# BEP33_2panel_v2b_DESKTOP-T8KKGMJ_Mai-19-.net
KiCad netlist of a schematic drawn in EAGLE
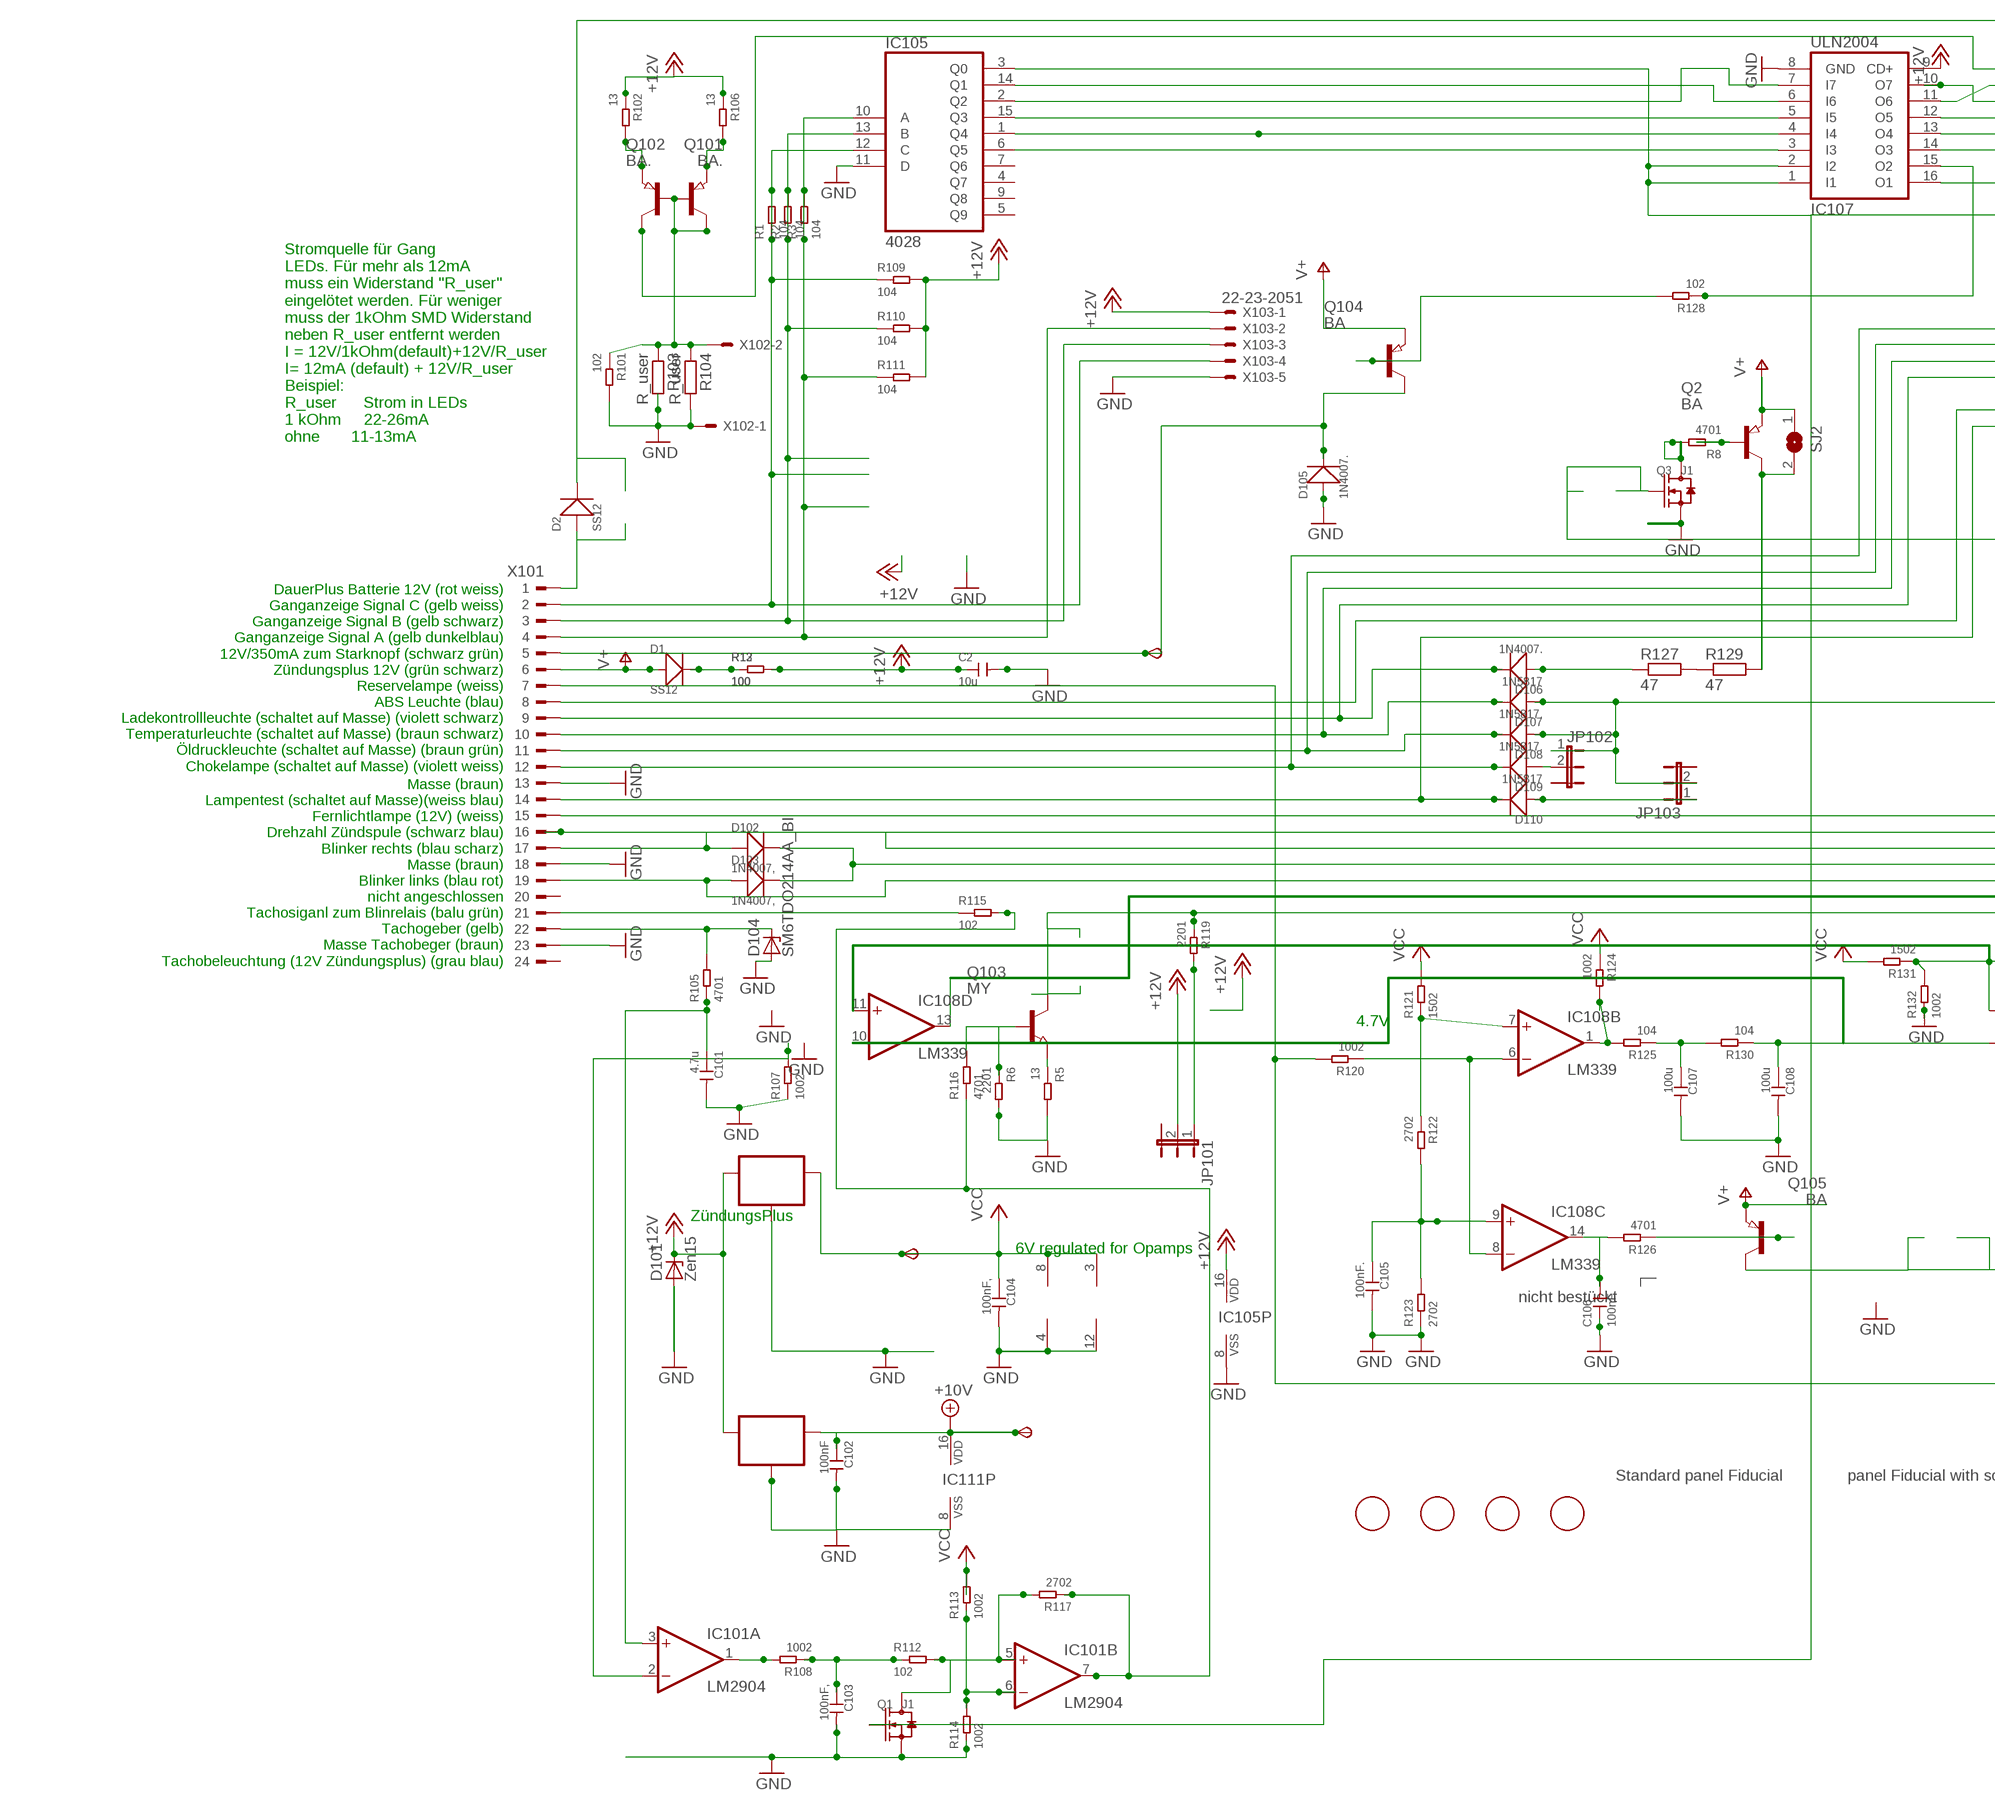
[diagram p0: schematic, sheet 1, part 1 of 2]
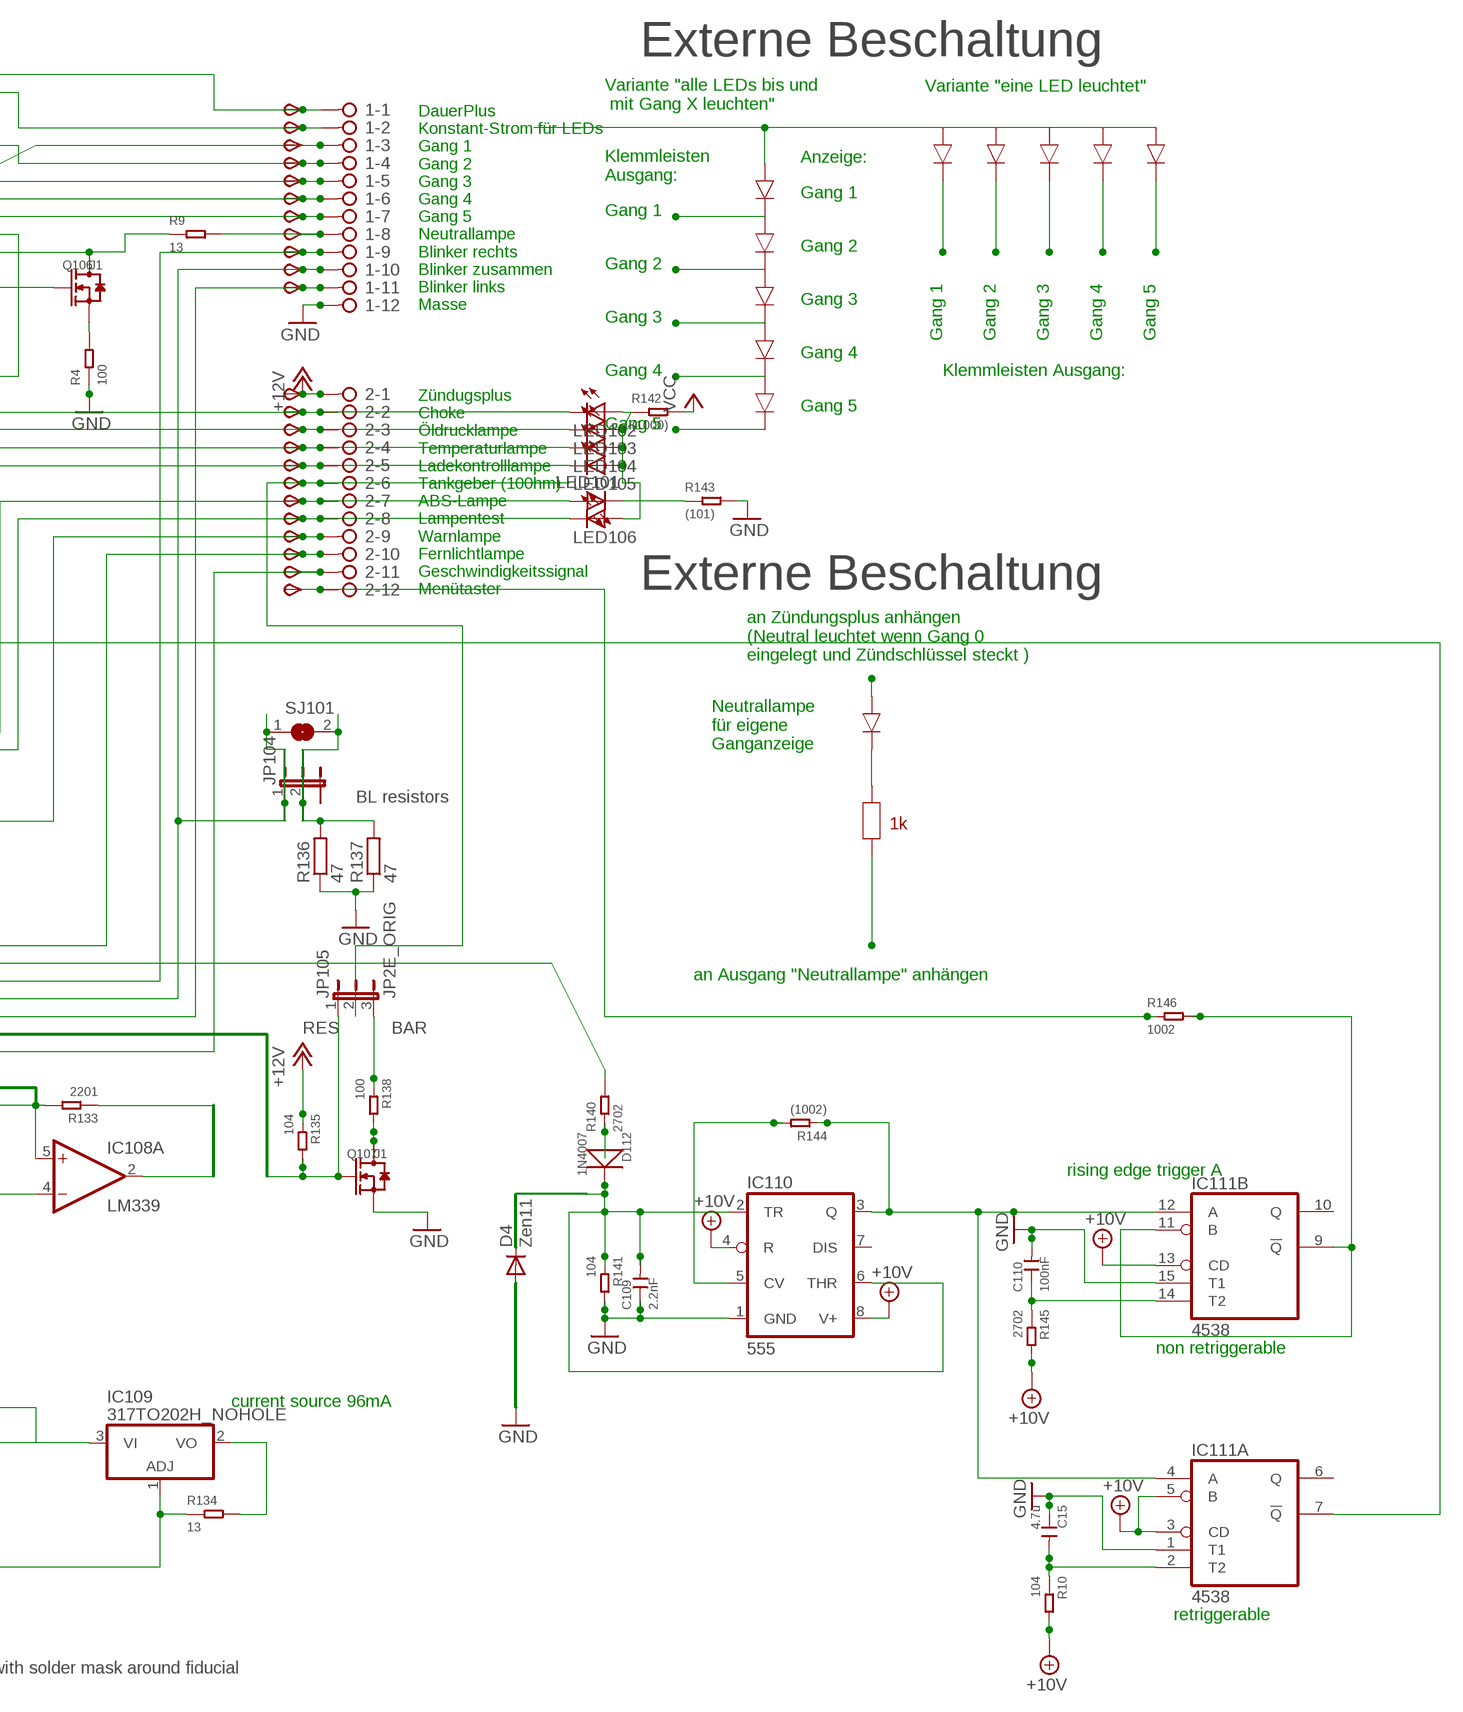
[diagram p1: schematic, sheet 1, part 2 of 2]

(export (version "E")
  (design (tool "Eeschema 10.0.6"))
  (components
    (comp (ref "1")
      (value "2081-1132")
      (footprint "eagle-import:12-PIN")
      (libsource (lib "eagle-import") (part "2081-1132"))
    )
    (comp (ref "2")
      (value "2081-1132")
      (footprint "eagle-import:12-PIN")
      (libsource (lib "eagle-import") (part "2081-1132"))
    )
    (comp (ref "6V")
      (value "TPSB2.0")
      (footprint "eagle-import:B2.0")
      (libsource (lib "eagle-import") (part "TPSB2.0"))
    )
    (comp (ref "10V")
      (value "TPSB2.0")
      (footprint "eagle-import:B2.0")
      (libsource (lib "eagle-import") (part "TPSB2.0"))
    )
    (comp (ref "C2")
      (value "10u")
      (footprint "eagle-import:C1206")
      (fields (field (name "MPN") "GRM31CR60J107ME39L"))
      (libsource (lib "eagle-import") (part "CERAMIC-100UF-6.3V-20%-X5R(1206)"))
    )
    (comp (ref "C15")
      (value "4.7u")
      (footprint "eagle-import:C0805")
      (fields (field (name "MPN") "CC0805KKX5R8BB475"))
      (libsource (lib "eagle-import") (part "CERAMIC-4.7UF-25V-10%-X5R(0805)"))
    )
    (comp (ref "C101")
      (value "4.7u")
      (footprint "eagle-import:C0805")
      (fields (field (name "MPN") "CC0805KKX5R8BB475"))
      (libsource (lib "eagle-import") (part "CERAMIC-4.7UF-25V-10%-X5R(0805)"))
    )
    (comp (ref "C102")
      (value "100nF")
      (footprint "eagle-import:C0805")
      (fields (field (name "MPN") "CC0805KRX7R9BB104"))
      (libsource (lib "eagle-import") (part "CERAMIC-100NF-50V-10%-X7R(0805)"))
    )
    (comp (ref "C103")
      (value "100nF,")
      (footprint "eagle-import:C0805")
      (fields (field (name "MPN") "CC0805KRX7R9BB104"))
      (libsource (lib "eagle-import") (part "CERAMIC-100NF-50V-10%-X7R(0805)"))
    )
    (comp (ref "C104")
      (value "100nF,")
      (footprint "eagle-import:C0805")
      (fields (field (name "MPN") "CC0805KRX7R9BB104"))
      (libsource (lib "eagle-import") (part "CERAMIC-100NF-50V-10%-X7R(0805)"))
    )
    (comp (ref "C105")
      (value "100nF.")
      (footprint "eagle-import:C0805")
      (fields (field (name "MPN") "CC0805KRX7R9BB104"))
      (libsource (lib "eagle-import") (part "CERAMIC-100NF-50V-10%-X7R(0805)"))
    )
    (comp (ref "C106")
      (value "100nF.")
      (footprint "eagle-import:C0805")
      (fields (field (name "MPN") "CC0805KRX7R9BB104"))
      (libsource (lib "eagle-import") (part "CERAMIC-100NF-50V-10%-X7R(0805)"))
    )
    (comp (ref "C107")
      (value "100u")
      (footprint "eagle-import:C1206")
      (fields (field (name "MPN") "GRM31CR60J107ME39L"))
      (libsource (lib "eagle-import") (part "CERAMIC-100UF-6.3V-20%-X5R(1206)"))
    )
    (comp (ref "C108")
      (value "100u")
      (footprint "eagle-import:C1206")
      (fields (field (name "MPN") "GRM31CR60J107ME39L"))
      (libsource (lib "eagle-import") (part "CERAMIC-100UF-6.3V-20%-X5R(1206)"))
    )
    (comp (ref "C109")
      (value "2.2nF")
      (footprint "eagle-import:C0805")
      (fields (field (name "MPN") "CC0805KRX7R9BB104"))
      (libsource (lib "eagle-import") (part "CERAMIC-100NF-50V-10%-X7R(0805)"))
    )
    (comp (ref "C110")
      (value "100nF")
      (footprint "eagle-import:C0805")
      (fields (field (name "MPN") "CC0805KRX7R9BB104"))
      (libsource (lib "eagle-import") (part "CERAMIC-100NF-50V-10%-X7R(0805)"))
    )
    (comp (ref "D1")
      (value "SS12")
      (footprint "eagle-import:DO-214AC_SLIM")
      (libsource (lib "eagle-import") (part "DIODE-GEN-PURPOSE-1KV-1A(DO-214AC)DO-214AC/1206"))
    )
    (comp (ref "D2")
      (value "SS12")
      (footprint "eagle-import:DO-214AC_SLIM")
      (libsource (lib "eagle-import") (part "DIODE-GEN-PURPOSE-1KV-1A(DO-214AC)DO-214AC/1206"))
    )
    (comp (ref "D4")
      (value "Zen11")
      (footprint "eagle-import:SOD-123_MINI-SMA")
      (libsource (lib "eagle-import") (part "CGRM400-G1"))
    )
    (comp (ref "D101")
      (value "Zen15")
      (footprint "eagle-import:DO214AA")
      (libsource (lib "eagle-import") (part "SM6T"))
    )
    (comp (ref "D102")
      (value "1N4007,")
      (footprint "eagle-import:DO-214AC")
      (fields (field (name "MPN") "1N4007"))
      (libsource (lib "eagle-import") (part "DIODE-GEN-PURPOSE-1KV-1A(DO-214AC)"))
    )
    (comp (ref "D103")
      (value "1N4007,")
      (footprint "eagle-import:DO-214AC")
      (fields (field (name "MPN") "1N4007"))
      (libsource (lib "eagle-import") (part "DIODE-GEN-PURPOSE-1KV-1A(DO-214AC)"))
    )
    (comp (ref "D104")
      (value "SM6TDO214AA_BI")
      (footprint "eagle-import:DO214AA_BI")
      (libsource (lib "eagle-import") (part "SM6TDO214AA_BI"))
    )
    (comp (ref "D105")
      (value "1N4007.")
      (footprint "eagle-import:DO-214AC")
      (fields (field (name "MPN") "1N4007"))
      (libsource (lib "eagle-import") (part "DIODE-GEN-PURPOSE-1KV-1A(DO-214AC)"))
    )
    (comp (ref "D106")
      (value "1N4007.")
      (footprint "eagle-import:DO-214AC")
      (fields (field (name "MPN") "1N4007"))
      (libsource (lib "eagle-import") (part "DIODE-GEN-PURPOSE-1KV-1A(DO-214AC)"))
    )
    (comp (ref "D107")
      (value "1N5817")
      (footprint "eagle-import:DO-214AC_SLIM")
      (libsource (lib "eagle-import") (part "DIODE-GEN-PURPOSE-1KV-1A(DO-214AC)DO-214AC/1206"))
    )
    (comp (ref "D108")
      (value "1N5817.")
      (footprint "eagle-import:DO-214AC_SLIM")
      (libsource (lib "eagle-import") (part "DIODE-GEN-PURPOSE-1KV-1A(DO-214AC)DO-214AC/1206"))
    )
    (comp (ref "D109")
      (value "1N5817.")
      (footprint "eagle-import:DO-214AC_SLIM")
      (libsource (lib "eagle-import") (part "DIODE-GEN-PURPOSE-1KV-1A(DO-214AC)DO-214AC/1206"))
    )
    (comp (ref "D110")
      (value "1N5817")
      (footprint "eagle-import:DO-214AC_SLIM")
      (libsource (lib "eagle-import") (part "DIODE-GEN-PURPOSE-1KV-1A(DO-214AC)DO-214AC/1206"))
    )
    (comp (ref "D112")
      (value "1N4007")
      (footprint "eagle-import:DO-214AC")
      (libsource (lib "eagle-import") (part "DIODE-GEN-PURPOSE-1KV-1A(DO-214AC)"))
    )
    (comp (ref "FID101")
      (value "FIDUCIAL")
      (footprint "eagle-import:FIDUCIAL_1MM")
      (libsource (lib "eagle-import") (part "FIDUCIAL"))
    )
    (comp (ref "FID102")
      (value "FIDUCIAL")
      (footprint "eagle-import:FIDUCIAL_1MM")
      (libsource (lib "eagle-import") (part "FIDUCIAL"))
    )
    (comp (ref "FID103")
      (value "FIDUCIAL")
      (footprint "eagle-import:FIDUCIAL_1MM")
      (libsource (lib "eagle-import") (part "FIDUCIAL"))
    )
    (comp (ref "FID104")
      (value "FIDUCIAL")
      (footprint "eagle-import:FIDUCIAL_1MM")
      (libsource (lib "eagle-import") (part "FIDUCIAL"))
    )
    (comp (ref "IC101")
      (value "LM2904")
      (footprint "eagle-import:SO08")
      (libsource (lib "eagle-import") (part "LM358D"))
    )
    (comp (ref "IC102")
      (value "78L06")
      (footprint "eagle-import:SOT89_ROUND")
      (libsource (lib "eagle-import") (part "78LXXSOT89_ROUND"))
    )
    (comp (ref "IC104")
      (value "78L10")
      (footprint "eagle-import:SOT89_ROUND")
      (libsource (lib "eagle-import") (part "78LXXSOT89_ROUND"))
    )
    (comp (ref "IC105")
      (value "4028")
      (footprint "eagle-import:SO16")
      (libsource (lib "eagle-import") (part "4028D"))
    )
    (comp (ref "IC107")
      (value "ULN2004")
      (footprint "eagle-import:SO16")
      (libsource (lib "eagle-import") (part "ULN2004AD"))
    )
    (comp (ref "IC108")
      (value "LM339")
      (footprint "eagle-import:SO14")
      (libsource (lib "eagle-import") (part "LM339D"))
    )
    (comp (ref "IC109")
      (value "317TO202H_NOHOLE")
      (footprint "eagle-import:TO220H_NOHOLE")
      (libsource (lib "eagle-import") (part "317TO202H_NOHOLE"))
    )
    (comp (ref "IC110")
      (value "555")
      (footprint "eagle-import:SO08")
      (libsource (lib "eagle-import") (part "555DNE"))
    )
    (comp (ref "IC111")
      (value "4538")
      (footprint "eagle-import:SO16")
      (libsource (lib "eagle-import") (part "4538D"))
    )
    (comp (ref "JP101")
      (value "JP2EJP2_SMALLPADS")
      (footprint "eagle-import:JP2_SMALLPADS")
      (libsource (lib "eagle-import") (part "JP2EJP2_SMALLPADS"))
    )
    (comp (ref "JP102")
      (value "JP2EJP2_SMALLPADS")
      (footprint "eagle-import:JP2_SMALLPADS")
      (libsource (lib "eagle-import") (part "JP2EJP2_SMALLPADS"))
    )
    (comp (ref "JP103")
      (value "JP2EJP2_SMALLPADS")
      (footprint "eagle-import:JP2_SMALLPADS")
      (libsource (lib "eagle-import") (part "JP2EJP2_SMALLPADS"))
    )
    (comp (ref "JP104")
      (value "JP2EJP2_SMALLPADS")
      (footprint "eagle-import:JP2_SMALLPADS")
      (libsource (lib "eagle-import") (part "JP2EJP2_SMALLPADS"))
    )
    (comp (ref "JP105")
      (value "JP2E_ORIG")
      (footprint "eagle-import:JP2_ORIG_SMALLPADS")
      (libsource (lib "eagle-import") (part "JP2E_ORIG"))
    )
    (comp (ref "LED101")
      (value "LEDLD260")
      (footprint "eagle-import:LD260")
      (libsource (lib "eagle-import") (part "LEDLD260"))
    )
    (comp (ref "LED102")
      (value "LEDLD260")
      (footprint "eagle-import:LD260")
      (libsource (lib "eagle-import") (part "LEDLD260"))
    )
    (comp (ref "LED103")
      (value "LEDLD260")
      (footprint "eagle-import:LD260")
      (libsource (lib "eagle-import") (part "LEDLD260"))
    )
    (comp (ref "LED104")
      (value "LEDLD260")
      (footprint "eagle-import:LD260")
      (libsource (lib "eagle-import") (part "LEDLD260"))
    )
    (comp (ref "LED105")
      (value "LEDLD260")
      (footprint "eagle-import:LD260")
      (libsource (lib "eagle-import") (part "LEDLD260"))
    )
    (comp (ref "LED106")
      (value "LEDLD260")
      (footprint "eagle-import:LD260")
      (libsource (lib "eagle-import") (part "LEDLD260"))
    )
    (comp (ref "Q1")
      (value "J1")
      (footprint "eagle-import:SOT-23")
      (fields (field (name "MPN") "BSS138W-7-F"))
      (libsource (lib "eagle-import") (part "SMD-MOSFET-N-CH-50V-200MA-BSS138W-7-F(SOT-23)"))
    )
    (comp (ref "Q2")
      (value "BA")
      (footprint "eagle-import:SOT89")
      (libsource (lib "eagle-import") (part "PNP-TRANSISTOR_SOT89"))
    )
    (comp (ref "Q3")
      (value "J1")
      (footprint "eagle-import:SOT-23")
      (fields (field (name "MPN") "BSS138W-7-F"))
      (libsource (lib "eagle-import") (part "SMD-MOSFET-N-CH-50V-200MA-BSS138W-7-F(SOT-23)"))
    )
    (comp (ref "Q101")
      (value "BA.")
      (footprint "eagle-import:SOT89")
      (libsource (lib "eagle-import") (part "PNP-TRANSISTOR_SOT89"))
    )
    (comp (ref "Q102")
      (value "BA.")
      (footprint "eagle-import:SOT89")
      (libsource (lib "eagle-import") (part "PNP-TRANSISTOR_SOT89"))
    )
    (comp (ref "Q103")
      (value "MY")
      (footprint "eagle-import:SOT89")
      (libsource (lib "eagle-import") (part "NPN-TRANSISTOR_SOT89"))
    )
    (comp (ref "Q104")
      (value "BA")
      (footprint "eagle-import:SOT89")
      (libsource (lib "eagle-import") (part "PNP-TRANSISTOR_SOT89"))
    )
    (comp (ref "Q105")
      (value "BA")
      (footprint "eagle-import:SOT89")
      (libsource (lib "eagle-import") (part "PNP-TRANSISTOR_SOT89"))
    )
    (comp (ref "Q106")
      (value "J1")
      (footprint "eagle-import:SOT-23")
      (fields (field (name "MPN") "BSS138W-7-F"))
      (libsource (lib "eagle-import") (part "SMD-MOSFET-N-CH-50V-200MA-BSS138W-7-F(SOT-23)"))
    )
    (comp (ref "Q107")
      (value "J1")
      (footprint "eagle-import:SOT-23")
      (fields (field (name "MPN") "BSS138W-7-F"))
      (libsource (lib "eagle-import") (part "SMD-MOSFET-N-CH-50V-200MA-BSS138W-7-F(SOT-23)"))
    )
    (comp (ref "R1")
      (value "104")
      (footprint "eagle-import:R0805")
      (fields (field (name "MPN") "RC0805FR-0710KL"))
      (libsource (lib "eagle-import") (part "SMD-RES-10K-1%-1/8W(0805)"))
    )
    (comp (ref "R2")
      (value "104")
      (footprint "eagle-import:R0805")
      (fields (field (name "MPN") "RC0805FR-0710KL"))
      (libsource (lib "eagle-import") (part "SMD-RES-10K-1%-1/8W(0805)"))
    )
    (comp (ref "R3")
      (value "104")
      (footprint "eagle-import:R0805")
      (fields (field (name "MPN") "RC0805FR-0710KL"))
      (libsource (lib "eagle-import") (part "SMD-RES-10K-1%-1/8W(0805)"))
    )
    (comp (ref "R4")
      (value "100")
      (footprint "eagle-import:R0805")
      (fields (field (name "MPN") "RC0805JR-07220RL"))
      (libsource (lib "eagle-import") (part "SMD-RES-220R-5%-1/8W(0805)"))
    )
    (comp (ref "R5")
      (value "13")
      (footprint "eagle-import:R1206")
      (fields (field (name "MPN") "RC1206JR-0713RL"))
      (libsource (lib "eagle-import") (part "SMD-RES-13R-5%-1/4W(1206)"))
    )
    (comp (ref "R6")
      (value "2201")
      (footprint "eagle-import:R0805")
      (fields (field (name "MPN") "RC0805JR-071KL"))
      (libsource (lib "eagle-import") (part "SMD-RES-1K-5%-1/8W(0805)"))
    )
    (comp (ref "R8")
      (value "4701")
      (footprint "eagle-import:R0805")
      (fields (field (name "MPN") "RC0805JR-074K7L"))
      (libsource (lib "eagle-import") (part "SMD-RES-4.7K-5%-1/8W(0805)"))
    )
    (comp (ref "R9")
      (value "13")
      (footprint "eagle-import:R1206")
      (fields (field (name "MPN") "RC1206JR-0713RL"))
      (libsource (lib "eagle-import") (part "SMD-RES-13R-5%-1/4W(1206)"))
    )
    (comp (ref "R10")
      (value "104")
      (footprint "eagle-import:R0805")
      (fields (field (name "MPN") "RC0805JR-074K7L"))
      (libsource (lib "eagle-import") (part "SMD-RES-4.7K-5%-1/8W(0805)"))
    )
    (comp (ref "R12")
      (value "100")
      (footprint "eagle-import:R0805")
      (fields (field (name "MPN") "RC0805JR-072K2L"))
      (libsource (lib "eagle-import") (part "SMD-RES-2.2K-5%-1/8W(0805)"))
    )
    (comp (ref "R13")
      (value "100")
      (footprint "eagle-import:R0805")
      (fields (field (name "MPN") "RC0805JR-072K2L"))
      (libsource (lib "eagle-import") (part "SMD-RES-2.2K-5%-1/8W(0805)"))
    )
    (comp (ref "R101")
      (value "102")
      (footprint "eagle-import:R0805")
      (fields (field (name "MPN") "RC0805JR-071KL"))
      (libsource (lib "eagle-import") (part "SMD-RES-1K-5%-1/8W(0805)"))
    )
    (comp (ref "R102")
      (value "13")
      (footprint "eagle-import:R1206")
      (fields (field (name "MPN") "RC1206JR-0713RL"))
      (libsource (lib "eagle-import") (part "SMD-RES-13R-5%-1/4W(1206)"))
    )
    (comp (ref "R103")
      (value "R_user")
      (footprint "eagle-import:R0805")
      (libsource (lib "eagle-import") (part "R-EU_R0805"))
    )
    (comp (ref "R104")
      (value "R_user")
      (footprint "eagle-import:R0805")
      (libsource (lib "eagle-import") (part "R-EU_R0805"))
    )
    (comp (ref "R105")
      (value "4701")
      (footprint "eagle-import:R0805")
      (fields (field (name "MPN") "RC0805JR-074K7L"))
      (libsource (lib "eagle-import") (part "SMD-RES-4.7K-5%-1/8W(0805)"))
    )
    (comp (ref "R106")
      (value "13")
      (footprint "eagle-import:R1206")
      (fields (field (name "MPN") "RC1206JR-0713RL"))
      (libsource (lib "eagle-import") (part "SMD-RES-13R-5%-1/4W(1206)"))
    )
    (comp (ref "R107")
      (value "1002")
      (footprint "eagle-import:R0805")
      (fields (field (name "MPN") "RC0805FR-0710KL"))
      (libsource (lib "eagle-import") (part "SMD-RES-10K-1%-1/8W(0805)"))
    )
    (comp (ref "R108")
      (value "1002")
      (footprint "eagle-import:R0805")
      (fields (field (name "MPN") "RC0805FR-0710KL"))
      (libsource (lib "eagle-import") (part "SMD-RES-10K-1%-1/8W(0805)"))
    )
    (comp (ref "R109")
      (value "104")
      (footprint "eagle-import:R0805")
      (fields (field (name "MPN") "RC0805FR-0710KL"))
      (libsource (lib "eagle-import") (part "SMD-RES-10K-1%-1/8W(0805)"))
    )
    (comp (ref "R110")
      (value "104")
      (footprint "eagle-import:R0805")
      (fields (field (name "MPN") "RC0805FR-0710KL"))
      (libsource (lib "eagle-import") (part "SMD-RES-10K-1%-1/8W(0805)"))
    )
    (comp (ref "R111")
      (value "104")
      (footprint "eagle-import:R0805")
      (fields (field (name "MPN") "RC0805FR-0710KL"))
      (libsource (lib "eagle-import") (part "SMD-RES-10K-1%-1/8W(0805)"))
    )
    (comp (ref "R112")
      (value "102")
      (footprint "eagle-import:R0805")
      (fields (field (name "MPN") "RC0805JR-071KL"))
      (libsource (lib "eagle-import") (part "SMD-RES-1K-5%-1/8W(0805)"))
    )
    (comp (ref "R113")
      (value "1002")
      (footprint "eagle-import:R0805")
      (fields (field (name "MPN") "RC0805JR-071KL"))
      (libsource (lib "eagle-import") (part "SMD-RES-1K-5%-1/8W(0805)"))
    )
    (comp (ref "R114")
      (value "1002")
      (footprint "eagle-import:R0805")
      (fields (field (name "MPN") "RC0805JR-071KL"))
      (libsource (lib "eagle-import") (part "SMD-RES-1K-5%-1/8W(0805)"))
    )
    (comp (ref "R115")
      (value "102")
      (footprint "eagle-import:R0805")
      (fields (field (name "MPN") "RC0805JR-07220RL"))
      (libsource (lib "eagle-import") (part "SMD-RES-220R-5%-1/8W(0805)"))
    )
    (comp (ref "R116")
      (value "4701")
      (footprint "eagle-import:R0805")
      (fields (field (name "MPN") "RC0805JR-074K7L"))
      (libsource (lib "eagle-import") (part "SMD-RES-4.7K-5%-1/8W(0805)"))
    )
    (comp (ref "R117")
      (value "2702")
      (footprint "eagle-import:R0805")
      (fields (field (name "MPN") "RC0805JR-074K7L"))
      (libsource (lib "eagle-import") (part "SMD-RES-4.7K-5%-1/8W(0805)"))
    )
    (comp (ref "R119")
      (value "2201")
      (footprint "eagle-import:R0805")
      (fields (field (name "MPN") "RC0805JR-072K2L"))
      (libsource (lib "eagle-import") (part "SMD-RES-2.2K-5%-1/8W(0805)"))
    )
    (comp (ref "R120")
      (value "1002")
      (footprint "eagle-import:R0805")
      (fields (field (name "MPN") "RC0805FR-0710KL"))
      (libsource (lib "eagle-import") (part "SMD-RES-10K-1%-1/8W(0805)"))
    )
    (comp (ref "R121")
      (value "1502")
      (footprint "eagle-import:R0805")
      (fields (field (name "MPN") "RC0805FR-0710KL"))
      (libsource (lib "eagle-import") (part "SMD-RES-10K-1%-1/8W(0805)"))
    )
    (comp (ref "R122")
      (value "2702")
      (footprint "eagle-import:R0805")
      (fields (field (name "MPN") "RC0805JR-074K7L"))
      (libsource (lib "eagle-import") (part "SMD-RES-4.7K-5%-1/8W(0805)"))
    )
    (comp (ref "R123")
      (value "2702")
      (footprint "eagle-import:R0805")
      (fields (field (name "MPN") "RC0805JR-074K7L"))
      (libsource (lib "eagle-import") (part "SMD-RES-4.7K-5%-1/8W(0805)"))
    )
    (comp (ref "R124")
      (value "1002")
      (footprint "eagle-import:R0805")
      (fields (field (name "MPN") "RC0805FR-0710KL"))
      (libsource (lib "eagle-import") (part "SMD-RES-10K-1%-1/8W(0805)"))
    )
    (comp (ref "R125")
      (value "104")
      (footprint "eagle-import:R0805")
      (fields (field (name "MPN") "RC0805FR-0710KL"))
      (libsource (lib "eagle-import") (part "SMD-RES-10K-1%-1/8W(0805)"))
    )
    (comp (ref "R126")
      (value "4701")
      (footprint "eagle-import:R0805")
      (fields (field (name "MPN") "RC0805JR-074K7L"))
      (libsource (lib "eagle-import") (part "SMD-RES-4.7K-5%-1/8W(0805)"))
    )
    (comp (ref "R127")
      (value "47")
      (footprint "eagle-import:V235_17_1MM")
      (libsource (lib "eagle-import") (part "R-EU_V235/17_1MM"))
    )
    (comp (ref "R128")
      (value "102")
      (footprint "eagle-import:R0805")
      (fields (field (name "MPN") "RC0805JR-071KL"))
      (libsource (lib "eagle-import") (part "SMD-RES-1K-5%-1/8W(0805)"))
    )
    (comp (ref "R129")
      (value "47")
      (footprint "eagle-import:V235_17_1MM")
      (libsource (lib "eagle-import") (part "R-EU_V235/17_1MM"))
    )
    (comp (ref "R130")
      (value "104")
      (footprint "eagle-import:R0805")
      (fields (field (name "MPN") "RC0805FR-0710KL"))
      (libsource (lib "eagle-import") (part "SMD-RES-10K-1%-1/8W(0805)"))
    )
    (comp (ref "R131")
      (value "1502")
      (footprint "eagle-import:R0805")
      (fields (field (name "MPN") "RC0805FR-0710KL"))
      (libsource (lib "eagle-import") (part "SMD-RES-10K-1%-1/8W(0805)"))
    )
    (comp (ref "R132")
      (value "1002")
      (footprint "eagle-import:R0805")
      (fields (field (name "MPN") "RC0805FR-0710KL"))
      (libsource (lib "eagle-import") (part "SMD-RES-10K-1%-1/8W(0805)"))
    )
    (comp (ref "R133")
      (value "2201")
      (footprint "eagle-import:R0805")
      (fields (field (name "MPN") "RC0805JR-072K2L"))
      (libsource (lib "eagle-import") (part "SMD-RES-2.2K-5%-1/8W(0805)"))
    )
    (comp (ref "R134")
      (value "13")
      (footprint "eagle-import:R1206")
      (fields (field (name "MPN") "RC1206JR-0713RL"))
      (libsource (lib "eagle-import") (part "SMD-RES-13R-5%-1/4W(1206)"))
    )
    (comp (ref "R135")
      (value "104")
      (footprint "eagle-import:R0805")
      (fields (field (name "MPN") "RC0805FR-0710KL"))
      (libsource (lib "eagle-import") (part "SMD-RES-10K-1%-1/8W(0805)"))
    )
    (comp (ref "R136")
      (value "47")
      (footprint "eagle-import:V235_17_1MM")
      (libsource (lib "eagle-import") (part "R-EU_V235/17_1MM"))
    )
    (comp (ref "R137")
      (value "47")
      (footprint "eagle-import:V235_17_1MM")
      (libsource (lib "eagle-import") (part "R-EU_V235/17_1MM"))
    )
    (comp (ref "R138")
      (value "100")
      (footprint "eagle-import:R0805")
      (fields (field (name "MPN") "RC0805JR-072K2L"))
      (libsource (lib "eagle-import") (part "SMD-RES-2.2K-5%-1/8W(0805)"))
    )
    (comp (ref "R140")
      (value "2702")
      (footprint "eagle-import:R0805")
      (fields (field (name "MPN") "RC0805FR-0710KL"))
      (libsource (lib "eagle-import") (part "SMD-RES-10K-1%-1/8W(0805)"))
    )
    (comp (ref "R141")
      (value "104")
      (footprint "eagle-import:R0805")
      (fields (field (name "MPN") "RC0805FR-0710KL"))
      (libsource (lib "eagle-import") (part "SMD-RES-10K-1%-1/8W(0805)"))
    )
    (comp (ref "R142")
      (value "(1000)")
      (footprint "eagle-import:R0805")
      (fields (field (name "MPN") "RC0805JR-07100RL"))
      (libsource (lib "eagle-import") (part "SMD-RES-100R-5%-1/8W(0805)"))
    )
    (comp (ref "R143")
      (value "(101)")
      (footprint "eagle-import:R0805")
      (fields (field (name "MPN") "RC0805JR-07100RL"))
      (libsource (lib "eagle-import") (part "SMD-RES-100R-5%-1/8W(0805)"))
    )
    (comp (ref "R144")
      (value "(1002)")
      (footprint "eagle-import:R0805")
      (fields (field (name "MPN") "RC0805FR-0710KL"))
      (libsource (lib "eagle-import") (part "SMD-RES-10K-1%-1/8W(0805)"))
    )
    (comp (ref "R145")
      (value "2702")
      (footprint "eagle-import:R0805")
      (fields (field (name "MPN") "RC0805JR-074K7L"))
      (libsource (lib "eagle-import") (part "SMD-RES-4.7K-5%-1/8W(0805)"))
    )
    (comp (ref "R146")
      (value "1002")
      (footprint "eagle-import:R0805")
      (fields (field (name "MPN") "RC0805JR-074K7L"))
      (libsource (lib "eagle-import") (part "SMD-RES-4.7K-5%-1/8W(0805)"))
    )
    (comp (ref "SJ2") (value "SJ") (footprint "eagle-import:SJ") (libsource (lib "eagle-import") (part "SJ")))
    (comp (ref "SJ101")
      (value "SJ")
      (footprint "eagle-import:SJ")
      (libsource (lib "eagle-import") (part "solder-jumper_SJ"))
    )
    (comp (ref "START")
      (value "TPSB2.0")
      (footprint "eagle-import:B2.0")
      (libsource (lib "eagle-import") (part "TPSB2.0"))
    )
    (comp (ref "TP1")
      (value "TPSB2.0")
      (footprint "eagle-import:B2.0")
      (libsource (lib "eagle-import") (part "TPSB2.0"))
    )
    (comp (ref "TP2")
      (value "TPSB2.0")
      (footprint "eagle-import:B2.0")
      (libsource (lib "eagle-import") (part "TPSB2.0"))
    )
    (comp (ref "TP3")
      (value "TPSB2.0")
      (footprint "eagle-import:B2.0")
      (libsource (lib "eagle-import") (part "TPSB2.0"))
    )
    (comp (ref "TP4")
      (value "TPSB2.0")
      (footprint "eagle-import:B2.0")
      (libsource (lib "eagle-import") (part "TPSB2.0"))
    )
    (comp (ref "TP5")
      (value "TPSB2.0")
      (footprint "eagle-import:B2.0")
      (libsource (lib "eagle-import") (part "TPSB2.0"))
    )
    (comp (ref "TP6")
      (value "TPSB2.0")
      (footprint "eagle-import:B2.0")
      (libsource (lib "eagle-import") (part "TPSB2.0"))
    )
    (comp (ref "TP7")
      (value "TPSB2.0")
      (footprint "eagle-import:B2.0")
      (libsource (lib "eagle-import") (part "TPSB2.0"))
    )
    (comp (ref "TP8")
      (value "TPSB2.0")
      (footprint "eagle-import:B2.0")
      (libsource (lib "eagle-import") (part "TPSB2.0"))
    )
    (comp (ref "TP9")
      (value "TPSB2.0")
      (footprint "eagle-import:B2.0")
      (libsource (lib "eagle-import") (part "TPSB2.0"))
    )
    (comp (ref "TP10")
      (value "TPSB2.0")
      (footprint "eagle-import:B2.0")
      (libsource (lib "eagle-import") (part "TPSB2.0"))
    )
    (comp (ref "TP11")
      (value "TPSB2.0")
      (footprint "eagle-import:B2.0")
      (libsource (lib "eagle-import") (part "TPSB2.0"))
    )
    (comp (ref "TP12")
      (value "TPSB2.0")
      (footprint "eagle-import:B2.0")
      (libsource (lib "eagle-import") (part "TPSB2.0"))
    )
    (comp (ref "TP13")
      (value "TPSB2.0")
      (footprint "eagle-import:B2.0")
      (libsource (lib "eagle-import") (part "TPSB2.0"))
    )
    (comp (ref "TP16")
      (value "TPSB2.0")
      (footprint "eagle-import:B2.0")
      (libsource (lib "eagle-import") (part "TPSB2.0"))
    )
    (comp (ref "TP17")
      (value "TPSB2.0")
      (footprint "eagle-import:B2.0")
      (libsource (lib "eagle-import") (part "TPSB2.0"))
    )
    (comp (ref "TP18")
      (value "TPSB2.0")
      (footprint "eagle-import:B2.0")
      (libsource (lib "eagle-import") (part "TPSB2.0"))
    )
    (comp (ref "TP19")
      (value "TPSB2.0")
      (footprint "eagle-import:B2.0")
      (libsource (lib "eagle-import") (part "TPSB2.0"))
    )
    (comp (ref "TP21")
      (value "TPSB2.0")
      (footprint "eagle-import:B2.0")
      (libsource (lib "eagle-import") (part "TPSB2.0"))
    )
    (comp (ref "TP22")
      (value "TPSB2.0")
      (footprint "eagle-import:B2.0")
      (libsource (lib "eagle-import") (part "TPSB2.0"))
    )
    (comp (ref "TP23")
      (value "TPSB2.0")
      (footprint "eagle-import:B2.0")
      (libsource (lib "eagle-import") (part "TPSB2.0"))
    )
    (comp (ref "TP24")
      (value "TPSB1,27")
      (footprint "eagle-import:B1,27")
      (libsource (lib "eagle-import") (part "TPSB1,27"))
    )
    (comp (ref "TP25")
      (value "TPSB2.0")
      (footprint "eagle-import:B2.0")
      (libsource (lib "eagle-import") (part "TPSB2.0"))
    )
    (comp (ref "TP26")
      (value "TPSB2.0")
      (footprint "eagle-import:B2.0")
      (libsource (lib "eagle-import") (part "TPSB2.0"))
    )
    (comp (ref "X101")
      (value "CON_BMWV2")
      (footprint "eagle-import:24-PIN_V2")
      (libsource (lib "eagle-import") (part "CON_BMWV2"))
    )
    (comp (ref "X102")
      (value "22-23-2021")
      (footprint "eagle-import:22-23-2021")
      (fields (field (name "MF") "MOLEX"))
      (libsource (lib "eagle-import") (part "22-23-2021"))
    )
    (comp (ref "X103")
      (value "22-23-2051")
      (footprint "eagle-import:22-23-2051")
      (fields (field (name "MF") "MOLEX"))
      (libsource (lib "eagle-import") (part "22-23-2051"))
    )
  )
  (nets
    (net (code "1") (name "+10V") (class "Default")
      (node (ref "10V") (pin "TP") (pinfunction "PP_TP") (pintype "input"))
      (node (ref "C102") (pin "1") (pinfunction "1_1") (pintype "passive"))
      (node (ref "IC104") (pin "1") (pinfunction "OUT_1") (pintype "passive"))
      (node (ref "IC110") (pin "4") (pinfunction "R_4") (pintype "input"))
      (node (ref "IC110") (pin "8") (pinfunction "V+_8") (pintype "power_in"))
      (node (ref "IC111") (pin "13") (pinfunction "CD_13") (pintype "input"))
      (node (ref "IC111") (pin "16") (pinfunction "VDD_16") (pintype "power_in"))
      (node (ref "IC111") (pin "3") (pinfunction "CD_3") (pintype "input"))
      (node (ref "IC111") (pin "5") (pinfunction "B_5") (pintype "input"))
      (node (ref "R10") (pin "2") (pinfunction "2_2") (pintype "passive"))
      (node (ref "R145") (pin "2") (pinfunction "2_2") (pintype "passive"))
    )
    (net (code "2") (name "+12V") (class "Default")
      (node (ref "2") (pin "1") (pinfunction "KL_1") (pintype "passive"))
      (node (ref "C2") (pin "1") (pinfunction "1_1") (pintype "passive"))
      (node (ref "D101") (pin "C") (pinfunction "C_C") (pintype "passive"))
      (node (ref "IC102") (pin "3") (pinfunction "IN_3") (pintype "input"))
      (node (ref "IC104") (pin "3") (pinfunction "IN_3") (pintype "input"))
      (node (ref "IC105") (pin "16") (pinfunction "VDD_16") (pintype "power_in"))
      (node (ref "IC107") (pin "9") (pinfunction "CD+_9") (pintype "passive"))
      (node (ref "JP101") (pin "2") (pinfunction "2_2") (pintype "passive"))
      (node (ref "R102") (pin "1") (pinfunction "1_1") (pintype "passive"))
      (node (ref "R106") (pin "1") (pinfunction "1_1") (pintype "passive"))
      (node (ref "R109") (pin "2") (pinfunction "2_2") (pintype "passive"))
      (node (ref "R110") (pin "2") (pinfunction "2_2") (pintype "passive"))
      (node (ref "R111") (pin "2") (pinfunction "2_2") (pintype "passive"))
      (node (ref "R12") (pin "2") (pinfunction "2_2") (pintype "passive"))
      (node (ref "R13") (pin "2") (pinfunction "2_2") (pintype "passive"))
      (node (ref "R135") (pin "1") (pinfunction "1_1") (pintype "passive"))
      (node (ref "TP12") (pin "TP") (pinfunction "PP_TP") (pintype "input"))
      (node (ref "X103") (pin "1") (pinfunction "S_1") (pintype "passive"))
    )
    (net (code "3") (name "GND") (class "Default")
      (node (ref "1") (pin "12") (pinfunction "KL_12") (pintype "passive"))
      (node (ref "C101") (pin "2") (pinfunction "2_2") (pintype "passive"))
      (node (ref "C102") (pin "2") (pinfunction "2_2") (pintype "passive"))
      (node (ref "C103") (pin "2") (pinfunction "2_2") (pintype "passive"))
      (node (ref "C104") (pin "2") (pinfunction "2_2") (pintype "passive"))
      (node (ref "C105") (pin "2") (pinfunction "2_2") (pintype "passive"))
      (node (ref "C106") (pin "1") (pinfunction "1_1") (pintype "passive"))
      (node (ref "C107") (pin "2") (pinfunction "2_2") (pintype "passive"))
      (node (ref "C108") (pin "2") (pinfunction "2_2") (pintype "passive"))
      (node (ref "C109") (pin "1") (pinfunction "1_1") (pintype "passive"))
      (node (ref "C110") (pin "2") (pinfunction "2_2") (pintype "passive"))
      (node (ref "C15") (pin "1") (pinfunction "1_1") (pintype "passive"))
      (node (ref "C2") (pin "2") (pinfunction "2_2") (pintype "passive"))
      (node (ref "D101") (pin "A") (pinfunction "A_A") (pintype "passive"))
      (node (ref "D104") (pin "A") (pinfunction "A_A") (pintype "passive"))
      (node (ref "D105") (pin "1") (pinfunction "+_1") (pintype "passive"))
      (node (ref "D4") (pin "A") (pinfunction "A_A") (pintype "passive"))
      (node (ref "IC101") (pin "4") (pinfunction "V-_4") (pintype "power_in"))
      (node (ref "IC102") (pin "2") (pinfunction "GND_2") (pintype "input"))
      (node (ref "IC102") (pin "2@1") (pinfunction "GND_2@1") (pintype "input"))
      (node (ref "IC104") (pin "2") (pinfunction "GND_2") (pintype "input"))
      (node (ref "IC104") (pin "2@1") (pinfunction "GND_2@1") (pintype "input"))
      (node (ref "IC105") (pin "11") (pinfunction "D_11") (pintype "input"))
      (node (ref "IC105") (pin "8") (pinfunction "VSS_8") (pintype "power_in"))
      (node (ref "IC107") (pin "8") (pinfunction "GND_8") (pintype "power_in"))
      (node (ref "IC108") (pin "12") (pinfunction "GND_12") (pintype "power_in"))
      (node (ref "IC110") (pin "1") (pinfunction "GND_1") (pintype "power_in"))
      (node (ref "IC111") (pin "1") (pinfunction "T1_1") (pintype "input"))
      (node (ref "IC111") (pin "15") (pinfunction "T1_15") (pintype "input"))
      (node (ref "IC111") (pin "8") (pinfunction "VSS_8") (pintype "power_in"))
      (node (ref "Q1") (pin "2") (pinfunction "S_2") (pintype "passive"))
      (node (ref "Q107") (pin "2") (pinfunction "S_2") (pintype "passive"))
      (node (ref "Q3") (pin "2") (pinfunction "S_2") (pintype "passive"))
      (node (ref "R101") (pin "2") (pinfunction "2_2") (pintype "passive"))
      (node (ref "R103") (pin "2") (pinfunction "2_2") (pintype "passive"))
      (node (ref "R104") (pin "2") (pinfunction "2_2") (pintype "passive"))
      (node (ref "R107") (pin "1") (pinfunction "1_1") (pintype "passive"))
      (node (ref "R114") (pin "1") (pinfunction "1_1") (pintype "passive"))
      (node (ref "R123") (pin "1") (pinfunction "1_1") (pintype "passive"))
      (node (ref "R132") (pin "1") (pinfunction "1_1") (pintype "passive"))
      (node (ref "R136") (pin "1") (pinfunction "1_1") (pintype "passive"))
      (node (ref "R137") (pin "1") (pinfunction "1_1") (pintype "passive"))
      (node (ref "R141") (pin "2") (pinfunction "2_2") (pintype "passive"))
      (node (ref "R143") (pin "2") (pinfunction "2_2") (pintype "passive"))
      (node (ref "R4") (pin "1") (pinfunction "1_1") (pintype "passive"))
      (node (ref "R5") (pin "2") (pinfunction "2_2") (pintype "passive"))
      (node (ref "R6") (pin "2") (pinfunction "2_2") (pintype "passive"))
      (node (ref "X101") (pin "13") (pinfunction "13_13") (pintype "passive"))
      (node (ref "X101") (pin "18") (pinfunction "18_18") (pintype "passive"))
      (node (ref "X101") (pin "23") (pinfunction "23_23") (pintype "passive"))
      (node (ref "X102") (pin "1") (pinfunction "S_1") (pintype "passive"))
      (node (ref "X103") (pin "5") (pinfunction "S_5") (pintype "passive"))
    )
    (net (code "4") (name "Net-(1A-KL)") (class "Default")
      (node (ref "1") (pin "1") (pinfunction "KL_1") (pintype "passive"))
      (node (ref "D2") (pin "2") (pinfunction "-_2") (pintype "passive"))
      (node (ref "TP1") (pin "TP") (pinfunction "PP_TP") (pintype "input"))
    )
    (net (code "5") (name "Net-(1B-KL)") (class "Default")
      (node (ref "1") (pin "10") (pinfunction "KL_10") (pintype "passive"))
      (node (ref "D102") (pin "2") (pinfunction "-_2") (pintype "passive"))
      (node (ref "D103") (pin "2") (pinfunction "-_2") (pintype "passive"))
      (node (ref "JP104") (pin "1") (pinfunction "1_1") (pintype "passive"))
      (node (ref "SJ101") (pin "1") (pinfunction "1_1") (pintype "passive"))
      (node (ref "TP10") (pin "TP") (pinfunction "PP_TP") (pintype "input"))
    )
    (net (code "6") (name "Net-(1C-KL)") (class "Default")
      (node (ref "1") (pin "11") (pinfunction "KL_11") (pintype "passive"))
      (node (ref "D103") (pin "1") (pinfunction "+_1") (pintype "passive"))
      (node (ref "TP11") (pin "TP") (pinfunction "PP_TP") (pintype "input"))
      (node (ref "X101") (pin "19") (pinfunction "19_19") (pintype "passive"))
    )
    (net (code "7") (name "Net-(1E-KL)") (class "Default")
      (node (ref "1") (pin "2") (pinfunction "KL_2") (pintype "passive"))
      (node (ref "Q101") (pin "2") (pinfunction "C_2") (pintype "passive"))
      (node (ref "TP2") (pin "TP") (pinfunction "PP_TP") (pintype "input"))
    )
    (net (code "8") (name "Net-(1F-KL)") (class "Default")
      (node (ref "1") (pin "3") (pinfunction "KL_3") (pintype "passive"))
      (node (ref "IC107") (pin "11") (pinfunction "O6_11") (pintype "open_collector"))
      (node (ref "TP3") (pin "TP") (pinfunction "PP_TP") (pintype "input"))
    )
    (net (code "9") (name "Net-(1G-KL)") (class "Default")
      (node (ref "1") (pin "4") (pinfunction "KL_4") (pintype "passive"))
      (node (ref "IC107") (pin "10") (pinfunction "O7_10") (pintype "open_collector"))
      (node (ref "TP4") (pin "TP") (pinfunction "PP_TP") (pintype "input"))
    )
    (net (code "10") (name "Net-(1H-KL)") (class "Default")
      (node (ref "1") (pin "5") (pinfunction "KL_5") (pintype "passive"))
      (node (ref "IC107") (pin "12") (pinfunction "O5_12") (pintype "open_collector"))
      (node (ref "TP5") (pin "TP") (pinfunction "PP_TP") (pintype "input"))
    )
    (net (code "11") (name "Net-(1I-KL)") (class "Default")
      (node (ref "1") (pin "6") (pinfunction "KL_6") (pintype "passive"))
      (node (ref "IC107") (pin "13") (pinfunction "O4_13") (pintype "open_collector"))
      (node (ref "TP6") (pin "TP") (pinfunction "PP_TP") (pintype "input"))
    )
    (net (code "12") (name "Net-(1J-KL)") (class "Default")
      (node (ref "1") (pin "7") (pinfunction "KL_7") (pintype "passive"))
      (node (ref "IC107") (pin "14") (pinfunction "O3_14") (pintype "open_collector"))
      (node (ref "TP7") (pin "TP") (pinfunction "PP_TP") (pintype "input"))
    )
    (net (code "13") (name "Net-(1K-KL)") (class "Default")
      (node (ref "1") (pin "8") (pinfunction "KL_8") (pintype "passive"))
      (node (ref "R9") (pin "2") (pinfunction "2_2") (pintype "passive"))
      (node (ref "TP8") (pin "TP") (pinfunction "PP_TP") (pintype "input"))
    )
    (net (code "14") (name "Net-(1L-KL)") (class "Default")
      (node (ref "1") (pin "9") (pinfunction "KL_9") (pintype "passive"))
      (node (ref "D102") (pin "1") (pinfunction "+_1") (pintype "passive"))
      (node (ref "TP9") (pin "TP") (pinfunction "PP_TP") (pintype "input"))
      (node (ref "X101") (pin "17") (pinfunction "17_17") (pintype "passive"))
    )
    (net (code "15") (name "Net-(2B-KL)") (class "Default")
      (node (ref "2") (pin "10") (pinfunction "KL_10") (pintype "passive"))
      (node (ref "TP25") (pin "TP") (pinfunction "PP_TP") (pintype "input"))
      (node (ref "X101") (pin "15") (pinfunction "15_15") (pintype "passive"))
    )
    (net (code "16") (name "Net-(2C-KL)") (class "Default")
      (node (ref "2") (pin "11") (pinfunction "KL_11") (pintype "passive"))
      (node (ref "Q103") (pin "2") (pinfunction "C_2") (pintype "passive"))
      (node (ref "R119") (pin "1") (pinfunction "1_1") (pintype "passive"))
      (node (ref "TP26") (pin "TP") (pinfunction "PP_TP") (pintype "input"))
    )
    (net (code "17") (name "Net-(2D-KL)") (class "Default")
      (node (ref "2") (pin "12") (pinfunction "KL_12") (pintype "passive"))
      (node (ref "R146") (pin "1") (pinfunction "1_1") (pintype "passive"))
      (node (ref "TP13") (pin "TP") (pinfunction "PP_TP") (pintype "input"))
    )
    (net (code "18") (name "Net-(2E-KL)") (class "Default")
      (node (ref "2") (pin "2") (pinfunction "KL_2") (pintype "passive"))
      (node (ref "D109") (pin "2") (pinfunction "-_2") (pintype "passive"))
      (node (ref "LED102") (pin "K") (pinfunction "C_K") (pintype "passive"))
      (node (ref "TP16") (pin "TP") (pinfunction "PP_TP") (pintype "input"))
      (node (ref "X101") (pin "12") (pinfunction "12_12") (pintype "passive"))
    )
    (net (code "19") (name "Net-(2F-KL)") (class "Default")
      (node (ref "2") (pin "3") (pinfunction "KL_3") (pintype "passive"))
      (node (ref "D108") (pin "2") (pinfunction "-_2") (pintype "passive"))
      (node (ref "LED103") (pin "K") (pinfunction "C_K") (pintype "passive"))
      (node (ref "TP17") (pin "TP") (pinfunction "PP_TP") (pintype "input"))
      (node (ref "X101") (pin "11") (pinfunction "11_11") (pintype "passive"))
    )
    (net (code "20") (name "Net-(2G-KL)") (class "Default")
      (node (ref "2") (pin "4") (pinfunction "KL_4") (pintype "passive"))
      (node (ref "D107") (pin "2") (pinfunction "-_2") (pintype "passive"))
      (node (ref "LED104") (pin "K") (pinfunction "C_K") (pintype "passive"))
      (node (ref "TP18") (pin "TP") (pinfunction "PP_TP") (pintype "input"))
      (node (ref "X101") (pin "10") (pinfunction "10_10") (pintype "passive"))
    )
    (net (code "21") (name "Net-(2H-KL)") (class "Default")
      (node (ref "2") (pin "5") (pinfunction "KL_5") (pintype "passive"))
      (node (ref "D106") (pin "2") (pinfunction "-_2") (pintype "passive"))
      (node (ref "LED105") (pin "K") (pinfunction "C_K") (pintype "passive"))
      (node (ref "TP19") (pin "TP") (pinfunction "PP_TP") (pintype "input"))
      (node (ref "X101") (pin "9") (pinfunction "9_9") (pintype "passive"))
    )
    (net (code "22") (name "Net-(2I-KL)") (class "Default")
      (node (ref "2") (pin "6") (pinfunction "KL_6") (pintype "passive"))
      (node (ref "JP105") (pin "2") (pinfunction "2_2") (pintype "passive"))
      (node (ref "TP21") (pin "TP") (pinfunction "PP_TP") (pintype "input"))
    )
    (net (code "23") (name "Net-(2J-KL)") (class "Default")
      (node (ref "2") (pin "7") (pinfunction "KL_7") (pintype "passive"))
      (node (ref "LED101") (pin "A") (pinfunction "A_A") (pintype "passive"))
      (node (ref "TP22") (pin "TP") (pinfunction "PP_TP") (pintype "input"))
      (node (ref "X101") (pin "8") (pinfunction "8_8") (pintype "passive"))
    )
    (net (code "24") (name "Net-(2K-KL)") (class "Default")
      (node (ref "2") (pin "8") (pinfunction "KL_8") (pintype "passive"))
      (node (ref "D110") (pin "2") (pinfunction "-_2") (pintype "passive"))
      (node (ref "LED106") (pin "K") (pinfunction "C_K") (pintype "passive"))
      (node (ref "TP23") (pin "TP") (pinfunction "PP_TP") (pintype "input"))
      (node (ref "X101") (pin "14") (pinfunction "14_14") (pintype "passive"))
    )
    (net (code "25") (name "Net-(2L-KL)") (class "Default")
      (node (ref "2") (pin "9") (pinfunction "KL_9") (pintype "passive"))
      (node (ref "D107") (pin "1") (pinfunction "+_1") (pintype "passive"))
      (node (ref "D108") (pin "1") (pinfunction "+_1") (pintype "passive"))
      (node (ref "JP102") (pin "1") (pinfunction "1_1") (pintype "passive"))
      (node (ref "JP103") (pin "2") (pinfunction "2_2") (pintype "passive"))
      (node (ref "TP24") (pin "TP") (pinfunction "PP_TP") (pintype "input"))
    )
    (net (code "26") (name "Net-(C103-Pad1)") (class "Default")
      (node (ref "C103") (pin "1") (pinfunction "1_1") (pintype "passive"))
      (node (ref "R108") (pin "1") (pinfunction "1_1") (pintype "passive"))
      (node (ref "R112") (pin "1") (pinfunction "1_1") (pintype "passive"))
    )
    (net (code "27") (name "Net-(C107-Pad1)") (class "Default")
      (node (ref "C107") (pin "1") (pinfunction "1_1") (pintype "passive"))
      (node (ref "R125") (pin "1") (pinfunction "1_1") (pintype "passive"))
      (node (ref "R130") (pin "2") (pinfunction "2_2") (pintype "passive"))
    )
    (net (code "28") (name "Net-(D1--)") (class "Default")
      (node (ref "D1") (pin "2") (pinfunction "-_2") (pintype "passive"))
      (node (ref "R12") (pin "1") (pinfunction "1_1") (pintype "passive"))
      (node (ref "R13") (pin "1") (pinfunction "1_1") (pintype "passive"))
    )
    (net (code "29") (name "Net-(D2-+)") (class "Default")
      (node (ref "D2") (pin "1") (pinfunction "+_1") (pintype "passive"))
      (node (ref "X101") (pin "1") (pinfunction "1_1") (pintype "passive"))
    )
    (net (code "30") (name "Net-(D104-PadC)") (class "Default")
      (node (ref "D104") (pin "C") (pinfunction "C_C") (pintype "passive"))
      (node (ref "R105") (pin "2") (pinfunction "2_2") (pintype "passive"))
      (node (ref "X101") (pin "22") (pinfunction "22_22") (pintype "passive"))
    )
    (net (code "31") (name "Net-(D105--)") (class "Default")
      (node (ref "D105") (pin "2") (pinfunction "-_2") (pintype "passive"))
      (node (ref "Q104") (pin "2") (pinfunction "C_2") (pintype "passive"))
      (node (ref "START") (pin "TP") (pinfunction "PP_TP") (pintype "input"))
      (node (ref "X101") (pin "5") (pinfunction "5_5") (pintype "passive"))
    )
    (net (code "32") (name "Net-(D106-+)") (class "Default")
      (node (ref "D106") (pin "1") (pinfunction "+_1") (pintype "passive"))
      (node (ref "R127") (pin "1") (pinfunction "1_1") (pintype "passive"))
    )
    (net (code "33") (name "Net-(D109-+)") (class "Default")
      (node (ref "D109") (pin "1") (pinfunction "+_1") (pintype "passive"))
      (node (ref "JP102") (pin "2") (pinfunction "2_2") (pintype "passive"))
    )
    (net (code "34") (name "Net-(D110-+)") (class "Default")
      (node (ref "D110") (pin "1") (pinfunction "+_1") (pintype "passive"))
      (node (ref "JP103") (pin "1") (pinfunction "1_1") (pintype "passive"))
    )
    (net (code "35") (name "Net-(D112-+)") (class "Default")
      (node (ref "D112") (pin "1") (pinfunction "+_1") (pintype "passive"))
      (node (ref "R140") (pin "1") (pinfunction "1_1") (pintype "passive"))
    )
    (net (code "36") (name "Net-(D112--)") (class "Default")
      (node (ref "C109") (pin "2") (pinfunction "2_2") (pintype "passive"))
      (node (ref "D112") (pin "2") (pinfunction "-_2") (pintype "passive"))
      (node (ref "D4") (pin "C") (pinfunction "C_C") (pintype "passive"))
      (node (ref "IC110") (pin "2") (pinfunction "TR_2") (pintype "input"))
      (node (ref "IC110") (pin "6") (pinfunction "THR_6") (pintype "input"))
      (node (ref "R141") (pin "1") (pinfunction "1_1") (pintype "passive"))
    )
    (net (code "37") (name "Net-(IC101A-+IN)") (class "Default")
      (node (ref "C101") (pin "1") (pinfunction "1_1") (pintype "passive"))
      (node (ref "IC101") (pin "3") (pinfunction "+IN_3") (pintype "input"))
      (node (ref "R105") (pin "1") (pinfunction "1_1") (pintype "passive"))
    )
    (net (code "38") (name "Net-(IC101A--IN)") (class "Default")
      (node (ref "IC101") (pin "2") (pinfunction "-IN_2") (pintype "input"))
      (node (ref "R107") (pin "2") (pinfunction "2_2") (pintype "passive"))
    )
    (net (code "39") (name "Net-(IC101A-OUT)") (class "Default")
      (node (ref "IC101") (pin "1") (pinfunction "OUT_1") (pintype "output"))
      (node (ref "R108") (pin "2") (pinfunction "2_2") (pintype "passive"))
    )
    (net (code "40") (name "Net-(IC101B-+IN)") (class "Default")
      (node (ref "IC101") (pin "5") (pinfunction "+IN_5") (pintype "input"))
      (node (ref "Q1") (pin "3") (pinfunction "D_3") (pintype "passive"))
      (node (ref "R112") (pin "2") (pinfunction "2_2") (pintype "passive"))
      (node (ref "R117") (pin "2") (pinfunction "2_2") (pintype "passive"))
    )
    (net (code "41") (name "Net-(IC101B--IN)") (class "Default")
      (node (ref "IC101") (pin "6") (pinfunction "-IN_6") (pintype "input"))
      (node (ref "R113") (pin "1") (pinfunction "1_1") (pintype "passive"))
      (node (ref "R114") (pin "2") (pinfunction "2_2") (pintype "passive"))
    )
    (net (code "42") (name "Net-(IC101B-OUT)") (class "Default")
      (node (ref "IC101") (pin "7") (pinfunction "OUT_7") (pintype "output"))
      (node (ref "R115") (pin "2") (pinfunction "2_2") (pintype "passive"))
      (node (ref "R116") (pin "1") (pinfunction "1_1") (pintype "passive"))
      (node (ref "R117") (pin "1") (pinfunction "1_1") (pintype "passive"))
    )
    (net (code "43") (name "Net-(IC105A-A)") (class "Default")
      (node (ref "IC105") (pin "10") (pinfunction "A_10") (pintype "input"))
      (node (ref "R111") (pin "1") (pinfunction "1_1") (pintype "passive"))
      (node (ref "R3") (pin "1") (pinfunction "1_1") (pintype "passive"))
      (node (ref "R3") (pin "2") (pinfunction "2_2") (pintype "passive"))
      (node (ref "X101") (pin "4") (pinfunction "4_4") (pintype "passive"))
      (node (ref "X103") (pin "2") (pinfunction "S_2") (pintype "passive"))
    )
    (net (code "44") (name "Net-(IC105A-B)") (class "Default")
      (node (ref "IC105") (pin "13") (pinfunction "B_13") (pintype "input"))
      (node (ref "R110") (pin "1") (pinfunction "1_1") (pintype "passive"))
      (node (ref "R2") (pin "1") (pinfunction "1_1") (pintype "passive"))
      (node (ref "R2") (pin "2") (pinfunction "2_2") (pintype "passive"))
      (node (ref "X101") (pin "3") (pinfunction "3_3") (pintype "passive"))
      (node (ref "X103") (pin "3") (pinfunction "S_3") (pintype "passive"))
    )
    (net (code "45") (name "Net-(IC105A-C)") (class "Default")
      (node (ref "IC105") (pin "12") (pinfunction "C_12") (pintype "input"))
      (node (ref "R1") (pin "1") (pinfunction "1_1") (pintype "passive"))
      (node (ref "R1") (pin "2") (pinfunction "2_2") (pintype "passive"))
      (node (ref "R109") (pin "1") (pinfunction "1_1") (pintype "passive"))
      (node (ref "X101") (pin "2") (pinfunction "2_2") (pintype "passive"))
      (node (ref "X103") (pin "4") (pinfunction "S_4") (pintype "passive"))
    )
    (net (code "46") (name "Net-(IC105A-Q0)") (class "Default")
      (node (ref "IC105") (pin "3") (pinfunction "Q0_3") (pintype "output"))
      (node (ref "IC107") (pin "1") (pinfunction "I1_1") (pintype "input"))
      (node (ref "IC107") (pin "2") (pinfunction "I2_2") (pintype "input"))
      (node (ref "Q1") (pin "1") (pinfunction "G_1") (pintype "passive"))
      (node (ref "Q106") (pin "1") (pinfunction "G_1") (pintype "passive"))
    )
    (net (code "47") (name "Net-(IC105A-Q1)") (class "Default")
      (node (ref "IC105") (pin "14") (pinfunction "Q1_14") (pintype "output"))
      (node (ref "IC107") (pin "6") (pinfunction "I6_6") (pintype "input"))
    )
    (net (code "48") (name "Net-(IC105A-Q2)") (class "Default")
      (node (ref "IC105") (pin "2") (pinfunction "Q2_2") (pintype "output"))
      (node (ref "IC107") (pin "7") (pinfunction "I7_7") (pintype "input"))
    )
    (net (code "49") (name "Net-(IC105A-Q3)") (class "Default")
      (node (ref "IC105") (pin "15") (pinfunction "Q3_15") (pintype "output"))
      (node (ref "IC107") (pin "5") (pinfunction "I5_5") (pintype "input"))
    )
    (net (code "50") (name "Net-(IC105A-Q4)") (class "Default")
      (node (ref "IC105") (pin "1") (pinfunction "Q4_1") (pintype "output"))
      (node (ref "IC107") (pin "4") (pinfunction "I4_4") (pintype "input"))
    )
    (net (code "51") (name "Net-(IC105A-Q5)") (class "Default")
      (node (ref "IC105") (pin "6") (pinfunction "Q5_6") (pintype "output"))
      (node (ref "IC107") (pin "3") (pinfunction "I3_3") (pintype "input"))
    )
    (net (code "52") (name "Net-(IC107-O1)") (class "Default")
      (node (ref "IC107") (pin "16") (pinfunction "O1_16") (pintype "open_collector"))
      (node (ref "Q106") (pin "3") (pinfunction "D_3") (pintype "passive"))
      (node (ref "R9") (pin "1") (pinfunction "1_1") (pintype "passive"))
    )
    (net (code "53") (name "Net-(IC107-O2)") (class "Default")
      (node (ref "IC107") (pin "15") (pinfunction "O2_15") (pintype "open_collector"))
      (node (ref "R128") (pin "1") (pinfunction "1_1") (pintype "passive"))
    )
    (net (code "54") (name "Net-(IC108A-+IN)") (class "Default")
      (node (ref "IC108") (pin "11") (pinfunction "+IN_11") (pintype "input"))
      (node (ref "IC108") (pin "5") (pinfunction "+IN_5") (pintype "input"))
      (node (ref "R131") (pin "1") (pinfunction "1_1") (pintype "passive"))
      (node (ref "R132") (pin "2") (pinfunction "2_2") (pintype "passive"))
      (node (ref "R133") (pin "2") (pinfunction "2_2") (pintype "passive"))
    )
    (net (code "55") (name "Net-(IC108A--IN)") (class "Default")
      (node (ref "C108") (pin "1") (pinfunction "1_1") (pintype "passive"))
      (node (ref "IC108") (pin "10") (pinfunction "-IN_10") (pintype "input"))
      (node (ref "IC108") (pin "4") (pinfunction "-IN_4") (pintype "input"))
      (node (ref "R130") (pin "1") (pinfunction "1_1") (pintype "passive"))
    )
    (net (code "56") (name "Net-(IC108A-OUT)") (class "Default")
      (node (ref "IC108") (pin "2") (pinfunction "OUT_2") (pintype "open_collector"))
      (node (ref "R133") (pin "1") (pinfunction "1_1") (pintype "passive"))
    )
    (net (code "57") (name "Net-(IC108B-+IN)") (class "Default")
      (node (ref "IC108") (pin "7") (pinfunction "+IN_7") (pintype "input"))
      (node (ref "R121") (pin "1") (pinfunction "1_1") (pintype "passive"))
      (node (ref "R122") (pin "1") (pinfunction "1_1") (pintype "passive"))
    )
    (net (code "58") (name "Net-(IC108B--IN)") (class "Default")
      (node (ref "IC108") (pin "6") (pinfunction "-IN_6") (pintype "input"))
      (node (ref "IC108") (pin "8") (pinfunction "-IN_8") (pintype "input"))
      (node (ref "R120") (pin "1") (pinfunction "1_1") (pintype "passive"))
    )
    (net (code "59") (name "Net-(IC108B-OUT)") (class "Default")
      (node (ref "IC108") (pin "1") (pinfunction "OUT_1") (pintype "open_collector"))
      (node (ref "R124") (pin "2") (pinfunction "2_2") (pintype "passive"))
      (node (ref "R125") (pin "2") (pinfunction "2_2") (pintype "passive"))
    )
    (net (code "60") (name "Net-(IC108C-+IN)") (class "Default")
      (node (ref "C105") (pin "1") (pinfunction "1_1") (pintype "passive"))
      (node (ref "IC108") (pin "9") (pinfunction "+IN_9") (pintype "input"))
      (node (ref "R122") (pin "2") (pinfunction "2_2") (pintype "passive"))
      (node (ref "R123") (pin "2") (pinfunction "2_2") (pintype "passive"))
    )
    (net (code "61") (name "Net-(IC108C-OUT)") (class "Default")
      (node (ref "C106") (pin "2") (pinfunction "2_2") (pintype "passive"))
      (node (ref "IC108") (pin "14") (pinfunction "OUT_14") (pintype "open_collector"))
      (node (ref "R126") (pin "2") (pinfunction "2_2") (pintype "passive"))
    )
    (net (code "62") (name "Net-(IC108D-OUT)") (class "Default")
      (node (ref "IC108") (pin "13") (pinfunction "OUT_13") (pintype "open_collector"))
      (node (ref "JP105") (pin "1") (pinfunction "1_1") (pintype "passive"))
      (node (ref "Q107") (pin "1") (pinfunction "G_1") (pintype "passive"))
      (node (ref "R135") (pin "2") (pinfunction "2_2") (pintype "passive"))
    )
    (net (code "63") (name "Net-(IC109-ADJ)") (class "Default")
      (node (ref "IC109") (pin "1") (pinfunction "ADJ_1") (pintype "input"))
      (node (ref "R120") (pin "2") (pinfunction "2_2") (pintype "passive"))
      (node (ref "R134") (pin "1") (pinfunction "1_1") (pintype "passive"))
      (node (ref "X101") (pin "7") (pinfunction "7_7") (pintype "passive"))
    )
    (net (code "64") (name "Net-(IC109-VI)") (class "Default")
      (node (ref "IC109") (pin "3") (pinfunction "VI_3") (pintype "input"))
      (node (ref "Q105") (pin "2") (pinfunction "C_2") (pintype "passive"))
    )
    (net (code "65") (name "Net-(IC109-VO)") (class "Default")
      (node (ref "IC109") (pin "2") (pinfunction "VO_2") (pintype "passive"))
      (node (ref "R134") (pin "2") (pinfunction "2_2") (pintype "passive"))
    )
    (net (code "66") (name "Net-(IC110-CV)") (class "Default")
      (node (ref "IC110") (pin "5") (pinfunction "CV_5") (pintype "input"))
      (node (ref "R144") (pin "2") (pinfunction "2_2") (pintype "passive"))
    )
    (net (code "67") (name "Net-(IC110-Q)") (class "Default")
      (node (ref "IC110") (pin "3") (pinfunction "Q_3") (pintype "output"))
      (node (ref "IC111") (pin "12") (pinfunction "A_12") (pintype "input"))
      (node (ref "IC111") (pin "4") (pinfunction "A_4") (pintype "input"))
      (node (ref "R144") (pin "1") (pinfunction "1_1") (pintype "passive"))
    )
    (net (code "68") (name "Net-(IC111A-T2)") (class "Default")
      (node (ref "C15") (pin "2") (pinfunction "2_2") (pintype "passive"))
      (node (ref "IC111") (pin "2") (pinfunction "T2_2") (pintype "input"))
      (node (ref "R10") (pin "1") (pinfunction "1_1") (pintype "passive"))
    )
    (net (code "69") (name "Net-(IC111A-~{Q})") (class "Default")
      (node (ref "IC111") (pin "7") (pinfunction "~{Q}_7") (pintype "output"))
      (node (ref "Q3") (pin "1") (pinfunction "G_1") (pintype "passive"))
    )
    (net (code "70") (name "Net-(IC111B-B)") (class "Default")
      (node (ref "IC111") (pin "11") (pinfunction "B_11") (pintype "input"))
      (node (ref "IC111") (pin "9") (pinfunction "~{Q}_9") (pintype "output"))
      (node (ref "R146") (pin "2") (pinfunction "2_2") (pintype "passive"))
    )
    (net (code "71") (name "Net-(IC111B-T2)") (class "Default")
      (node (ref "C110") (pin "1") (pinfunction "1_1") (pintype "passive"))
      (node (ref "IC111") (pin "14") (pinfunction "T2_14") (pintype "input"))
      (node (ref "R145") (pin "1") (pinfunction "1_1") (pintype "passive"))
    )
    (net (code "72") (name "Net-(JP101-Pad1)") (class "Default")
      (node (ref "JP101") (pin "1") (pinfunction "1_1") (pintype "passive"))
      (node (ref "R119") (pin "2") (pinfunction "2_2") (pintype "passive"))
    )
    (net (code "73") (name "Net-(JP104-Pad2)") (class "Default")
      (node (ref "JP104") (pin "2") (pinfunction "2_2") (pintype "passive"))
      (node (ref "R136") (pin "2") (pinfunction "2_2") (pintype "passive"))
      (node (ref "R137") (pin "2") (pinfunction "2_2") (pintype "passive"))
      (node (ref "SJ101") (pin "2") (pinfunction "2_2") (pintype "passive"))
    )
    (net (code "74") (name "Net-(JP105-Pad3)") (class "Default")
      (node (ref "JP105") (pin "3") (pinfunction "3_3") (pintype "passive"))
      (node (ref "R138") (pin "1") (pinfunction "1_1") (pintype "passive"))
    )
    (net (code "75") (name "Net-(LED101-C)") (class "Default")
      (node (ref "LED101") (pin "K") (pinfunction "C_K") (pintype "passive"))
      (node (ref "R143") (pin "1") (pinfunction "1_1") (pintype "passive"))
    )
    (net (code "76") (name "Net-(LED102-PadA)") (class "Default")
      (node (ref "LED102") (pin "A") (pinfunction "A_A") (pintype "passive"))
      (node (ref "LED103") (pin "A") (pinfunction "A_A") (pintype "passive"))
      (node (ref "LED104") (pin "A") (pinfunction "A_A") (pintype "passive"))
      (node (ref "LED105") (pin "A") (pinfunction "A_A") (pintype "passive"))
      (node (ref "LED106") (pin "A") (pinfunction "A_A") (pintype "passive"))
      (node (ref "R142") (pin "1") (pinfunction "1_1") (pintype "passive"))
    )
    (net (code "77") (name "Net-(Q2-B)") (class "Default")
      (node (ref "Q2") (pin "1") (pinfunction "B_1") (pintype "passive"))
      (node (ref "R8") (pin "1") (pinfunction "1_1") (pintype "passive"))
    )
    (net (code "78") (name "Net-(Q2-C)") (class "Default")
      (node (ref "Q2") (pin "2") (pinfunction "C_2") (pintype "passive"))
      (node (ref "R129") (pin "2") (pinfunction "2_2") (pintype "passive"))
      (node (ref "SJ2") (pin "2") (pinfunction "2_2") (pintype "passive"))
    )
    (net (code "79") (name "Net-(Q3-D)") (class "Default")
      (node (ref "Q3") (pin "3") (pinfunction "D_3") (pintype "passive"))
      (node (ref "R8") (pin "2") (pinfunction "2_2") (pintype "passive"))
    )
    (net (code "80") (name "Net-(Q101-B)") (class "Default")
      (node (ref "Q101") (pin "1") (pinfunction "B_1") (pintype "passive"))
      (node (ref "Q102") (pin "1") (pinfunction "B_1") (pintype "passive"))
      (node (ref "Q102") (pin "2") (pinfunction "C_2") (pintype "passive"))
      (node (ref "R101") (pin "1") (pinfunction "1_1") (pintype "passive"))
      (node (ref "R103") (pin "1") (pinfunction "1_1") (pintype "passive"))
      (node (ref "R104") (pin "1") (pinfunction "1_1") (pintype "passive"))
      (node (ref "X102") (pin "2") (pinfunction "S_2") (pintype "passive"))
    )
    (net (code "81") (name "Net-(Q101-E)") (class "Default")
      (node (ref "Q101") (pin "3") (pinfunction "E_3") (pintype "passive"))
      (node (ref "R102") (pin "2") (pinfunction "2_2") (pintype "passive"))
    )
    (net (code "82") (name "Net-(Q102-E)") (class "Default")
      (node (ref "Q102") (pin "3") (pinfunction "E_3") (pintype "passive"))
      (node (ref "R106") (pin "2") (pinfunction "2_2") (pintype "passive"))
    )
    (net (code "83") (name "Net-(Q103-B)") (class "Default")
      (node (ref "Q103") (pin "1") (pinfunction "B_1") (pintype "passive"))
      (node (ref "R116") (pin "2") (pinfunction "2_2") (pintype "passive"))
      (node (ref "R6") (pin "1") (pinfunction "1_1") (pintype "passive"))
    )
    (net (code "84") (name "Net-(Q103-E)") (class "Default")
      (node (ref "Q103") (pin "3") (pinfunction "E_3") (pintype "passive"))
      (node (ref "R5") (pin "1") (pinfunction "1_1") (pintype "passive"))
    )
    (net (code "85") (name "Net-(Q104-B)") (class "Default")
      (node (ref "Q104") (pin "1") (pinfunction "B_1") (pintype "passive"))
      (node (ref "R128") (pin "2") (pinfunction "2_2") (pintype "passive"))
    )
    (net (code "86") (name "Net-(Q105-B)") (class "Default")
      (node (ref "Q105") (pin "1") (pinfunction "B_1") (pintype "passive"))
      (node (ref "R126") (pin "1") (pinfunction "1_1") (pintype "passive"))
    )
    (net (code "87") (name "Net-(Q106-S)") (class "Default")
      (node (ref "Q106") (pin "2") (pinfunction "S_2") (pintype "passive"))
      (node (ref "R4") (pin "2") (pinfunction "2_2") (pintype "passive"))
    )
    (net (code "88") (name "Net-(Q107-D)") (class "Default")
      (node (ref "Q107") (pin "3") (pinfunction "D_3") (pintype "passive"))
      (node (ref "R138") (pin "2") (pinfunction "2_2") (pintype "passive"))
    )
    (net (code "89") (name "Net-(R115-Pad1)") (class "Default")
      (node (ref "R115") (pin "1") (pinfunction "1_1") (pintype "passive"))
      (node (ref "X101") (pin "21") (pinfunction "21_21") (pintype "passive"))
    )
    (net (code "90") (name "Net-(R127-Pad2)") (class "Default")
      (node (ref "R127") (pin "2") (pinfunction "2_2") (pintype "passive"))
      (node (ref "R129") (pin "1") (pinfunction "1_1") (pintype "passive"))
    )
    (net (code "91") (name "Net-(R140-Pad2)") (class "Default")
      (node (ref "R140") (pin "2") (pinfunction "2_2") (pintype "passive"))
      (node (ref "X101") (pin "16") (pinfunction "16_16") (pintype "passive"))
    )
    (net (code "92") (name "V+") (class "Default")
      (node (ref "D1") (pin "1") (pinfunction "+_1") (pintype "passive"))
      (node (ref "Q104") (pin "3") (pinfunction "E_3") (pintype "passive"))
      (node (ref "Q105") (pin "3") (pinfunction "E_3") (pintype "passive"))
      (node (ref "Q2") (pin "3") (pinfunction "E_3") (pintype "passive"))
      (node (ref "SJ2") (pin "1") (pinfunction "1_1") (pintype "passive"))
      (node (ref "X101") (pin "6") (pinfunction "6_6") (pintype "passive"))
    )
    (net (code "93") (name "VCC") (class "Default")
      (node (ref "6V") (pin "TP") (pinfunction "PP_TP") (pintype "input"))
      (node (ref "C104") (pin "1") (pinfunction "1_1") (pintype "passive"))
      (node (ref "IC101") (pin "8") (pinfunction "V+_8") (pintype "power_in"))
      (node (ref "IC102") (pin "1") (pinfunction "OUT_1") (pintype "passive"))
      (node (ref "IC108") (pin "3") (pinfunction "V+_3") (pintype "power_in"))
      (node (ref "R113") (pin "2") (pinfunction "2_2") (pintype "passive"))
      (node (ref "R121") (pin "2") (pinfunction "2_2") (pintype "passive"))
      (node (ref "R124") (pin "1") (pinfunction "1_1") (pintype "passive"))
      (node (ref "R131") (pin "2") (pinfunction "2_2") (pintype "passive"))
      (node (ref "R142") (pin "2") (pinfunction "2_2") (pintype "passive"))
    )
    (net (code "94") (name "unconnected-(IC105A-Q6-Pad7)") (class "Default")
      (node (ref "IC105") (pin "7") (pinfunction "Q6_7") (pintype "output"))
    )
    (net (code "95") (name "unconnected-(IC105A-Q7-Pad4)") (class "Default")
      (node (ref "IC105") (pin "4") (pinfunction "Q7_4") (pintype "output"))
    )
    (net (code "96") (name "unconnected-(IC105A-Q8-Pad9)") (class "Default")
      (node (ref "IC105") (pin "9") (pinfunction "Q8_9") (pintype "output"))
    )
    (net (code "97") (name "unconnected-(IC105A-Q9-Pad5)") (class "Default")
      (node (ref "IC105") (pin "5") (pinfunction "Q9_5") (pintype "output"))
    )
    (net (code "98") (name "unconnected-(IC110-DIS-Pad7)") (class "Default")
      (node (ref "IC110") (pin "7") (pinfunction "DIS_7") (pintype "input"))
    )
    (net (code "99") (name "unconnected-(IC111A-Q-Pad6)") (class "Default")
      (node (ref "IC111") (pin "6") (pinfunction "Q_6") (pintype "output"))
    )
    (net (code "100") (name "unconnected-(IC111B-Q-Pad10)") (class "Default")
      (node (ref "IC111") (pin "10") (pinfunction "Q_10") (pintype "output"))
    )
    (net (code "101") (name "unconnected-(X101-Pad20)") (class "Default")
      (node (ref "X101") (pin "20") (pinfunction "20_20") (pintype "passive"))
    )
    (net (code "102") (name "unconnected-(X101-Pad24)") (class "Default")
      (node (ref "X101") (pin "24") (pinfunction "24_24") (pintype "passive"))
    )
  )
)
